# untitled2.net
KiCad netlist of a schematic drawn in EAGLE
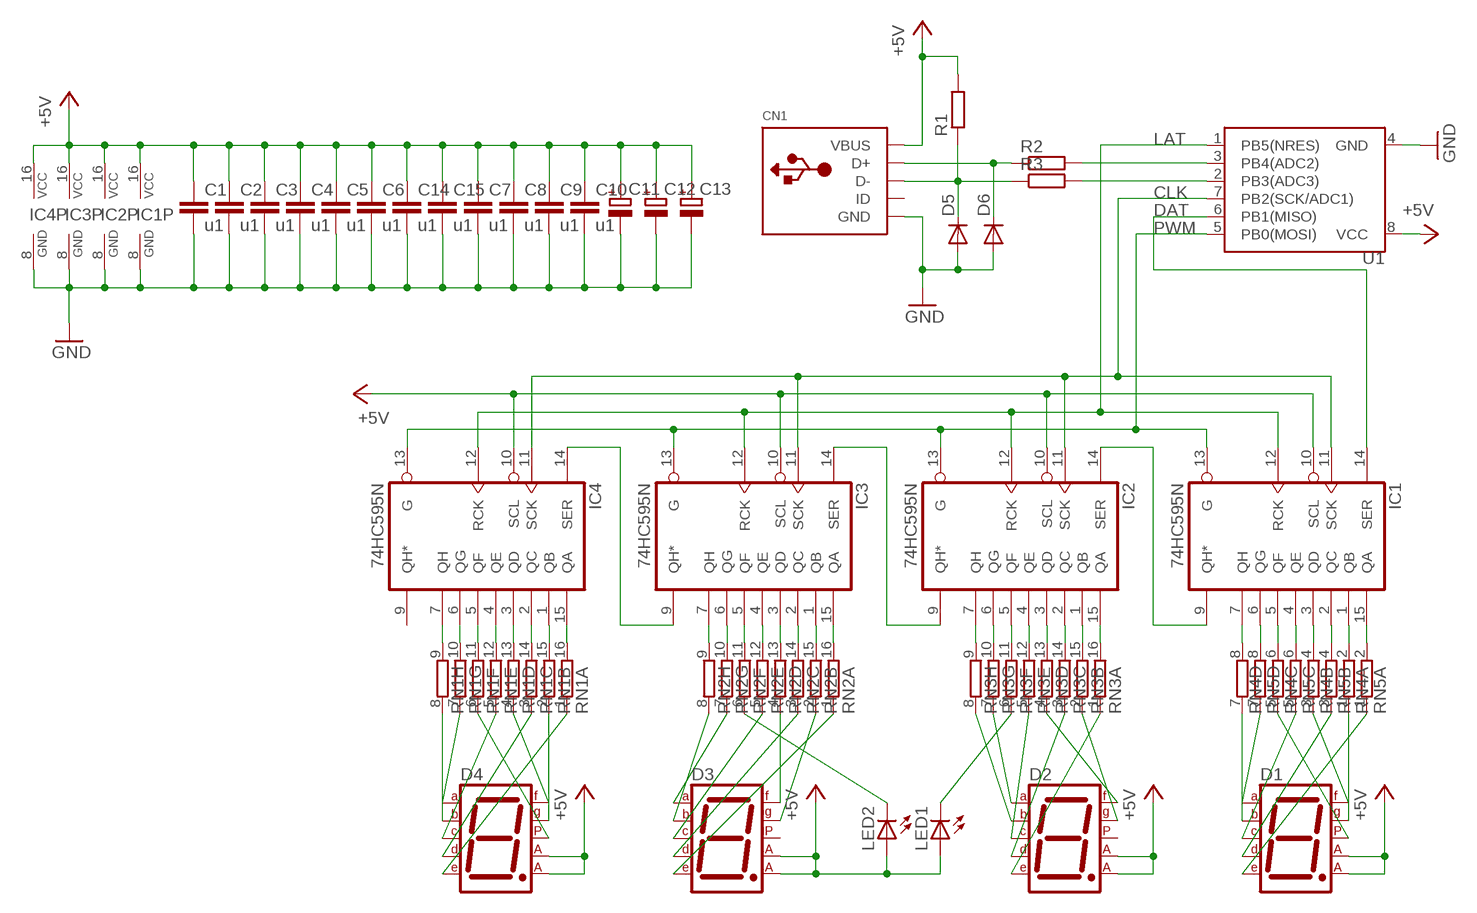
[diagram p0: schematic, sheet 1]

(export (version "E")
  (design (tool "Eeschema 10.0.6"))
  (components
    (comp (ref "C1")
      (value "u1")
      (footprint "eagle-import:C025-025X050")
      (libsource (lib "eagle-import") (part "C-EU025-025X050"))
    )
    (comp (ref "C2")
      (value "u1")
      (footprint "eagle-import:C025-025X050")
      (libsource (lib "eagle-import") (part "C-EU025-025X050"))
    )
    (comp (ref "C3")
      (value "u1")
      (footprint "eagle-import:C025-025X050")
      (libsource (lib "eagle-import") (part "C-EU025-025X050"))
    )
    (comp (ref "C4")
      (value "u1")
      (footprint "eagle-import:C025-025X050")
      (libsource (lib "eagle-import") (part "C-EU025-025X050"))
    )
    (comp (ref "C5")
      (value "u1")
      (footprint "eagle-import:C025-025X050")
      (libsource (lib "eagle-import") (part "C-EU025-025X050"))
    )
    (comp (ref "C6")
      (value "u1")
      (footprint "eagle-import:C025-025X050")
      (libsource (lib "eagle-import") (part "C-EU025-025X050"))
    )
    (comp (ref "C7")
      (value "u1")
      (footprint "eagle-import:C0805K")
      (libsource (lib "eagle-import") (part "C-EUC0805K"))
    )
    (comp (ref "C8")
      (value "u1")
      (footprint "eagle-import:C0805K")
      (libsource (lib "eagle-import") (part "C-EUC0805K"))
    )
    (comp (ref "C9")
      (value "u1")
      (footprint "eagle-import:C0805K")
      (libsource (lib "eagle-import") (part "C-EUC0805K"))
    )
    (comp (ref "C10")
      (value "u1")
      (footprint "eagle-import:C0805K")
      (libsource (lib "eagle-import") (part "C-EUC0805K"))
    )
    (comp (ref "C11")
      (value "CPOL-EUE1.8-4")
      (footprint "eagle-import:E1,8-4")
      (libsource (lib "eagle-import") (part "CPOL-EUE1.8-4"))
    )
    (comp (ref "C12")
      (value "CPOL-EUE2.5-7")
      (footprint "eagle-import:E2,5-7")
      (libsource (lib "eagle-import") (part "CPOL-EUE2.5-7"))
    )
    (comp (ref "C13")
      (value "CPOL-EUE2.5-7")
      (footprint "eagle-import:E2,5-7")
      (libsource (lib "eagle-import") (part "CPOL-EUE2.5-7"))
    )
    (comp (ref "C14")
      (value "u1")
      (footprint "eagle-import:C025-025X050")
      (libsource (lib "eagle-import") (part "C-EU025-025X050"))
    )
    (comp (ref "C15")
      (value "u1")
      (footprint "eagle-import:C025-025X050")
      (libsource (lib "eagle-import") (part "C-EU025-025X050"))
    )
    (comp (ref "CN1")
      (value "USBTHM")
      (footprint "eagle-import:USB-MINIB-THM")
      (libsource (lib "eagle-import") (part "USBTHM"))
    )
    (comp (ref "D1")
      (value "7SEG-CA")
      (footprint "eagle-import:7SEG-13")
      (libsource (lib "eagle-import") (part "7SEG-CA"))
    )
    (comp (ref "D2")
      (value "7SEG-CA")
      (footprint "eagle-import:7SEG-13")
      (libsource (lib "eagle-import") (part "7SEG-CA"))
    )
    (comp (ref "D3")
      (value "7SEG-CA")
      (footprint "eagle-import:7SEG-13")
      (libsource (lib "eagle-import") (part "7SEG-CA"))
    )
    (comp (ref "D4")
      (value "7SEG-CA")
      (footprint "eagle-import:7SEG-13")
      (libsource (lib "eagle-import") (part "7SEG-CA"))
    )
    (comp (ref "D5")
      (value "DIODE-D-7.5")
      (footprint "eagle-import:D-7.5")
      (libsource (lib "eagle-import") (part "DIODE-D-7.5"))
    )
    (comp (ref "D6")
      (value "DIODE-D-7.5")
      (footprint "eagle-import:D-7.5")
      (libsource (lib "eagle-import") (part "DIODE-D-7.5"))
    )
    (comp (ref "IC1")
      (value "74HC595N")
      (footprint "eagle-import:DIL16")
      (libsource (lib "eagle-import") (part "74595NHC"))
    )
    (comp (ref "IC2")
      (value "74HC595N")
      (footprint "eagle-import:DIL16")
      (libsource (lib "eagle-import") (part "74595NHC"))
    )
    (comp (ref "IC3")
      (value "74HC595N")
      (footprint "eagle-import:DIL16")
      (libsource (lib "eagle-import") (part "74595NHC"))
    )
    (comp (ref "IC4")
      (value "74HC595N")
      (footprint "eagle-import:DIL16")
      (libsource (lib "eagle-import") (part "74595NHC"))
    )
    (comp (ref "LED1")
      (value "LED3MM")
      (footprint "eagle-import:LED3MM")
      (libsource (lib "eagle-import") (part "LED3MM"))
    )
    (comp (ref "LED2")
      (value "LED3MM")
      (footprint "eagle-import:LED3MM")
      (libsource (lib "eagle-import") (part "LED3MM"))
    )
    (comp (ref "R1")
      (value "R-EU_0204/7")
      (footprint "eagle-import:0204_7")
      (libsource (lib "eagle-import") (part "R-EU_0204/7"))
    )
    (comp (ref "R2")
      (value "R-EU_0204/7")
      (footprint "eagle-import:0204_7")
      (libsource (lib "eagle-import") (part "R-EU_0204/7"))
    )
    (comp (ref "R3")
      (value "R-EU_0204/7")
      (footprint "eagle-import:0204_7")
      (libsource (lib "eagle-import") (part "R-EU_0204/7"))
    )
    (comp (ref "RN1")
      (value "8R-N")
      (footprint "eagle-import:DIL16")
      (libsource (lib "eagle-import") (part "8R-N"))
    )
    (comp (ref "RN2")
      (value "8R-N")
      (footprint "eagle-import:DIL16")
      (libsource (lib "eagle-import") (part "8R-N"))
    )
    (comp (ref "RN3")
      (value "8R-N")
      (footprint "eagle-import:DIL16")
      (libsource (lib "eagle-import") (part "8R-N"))
    )
    (comp (ref "RN4")
      (value "E4R")
      (footprint "eagle-import:SIL8")
      (libsource (lib "eagle-import") (part "E4R"))
    )
    (comp (ref "RN5")
      (value "E4R")
      (footprint "eagle-import:SIL8")
      (libsource (lib "eagle-import") (part "E4R"))
    )
    (comp (ref "U1")
      (value "ATTINY45ATTINYX5-20-DIP-GAP")
      (footprint "eagle-import:DIL08")
      (libsource (lib "eagle-import") (part "ATTINY45ATTINYX5-20-DIP-GAP"))
    )
  )
  (nets
    (net (code "1") (name "+5V") (class "Default")
      (node (ref "C1") (pin "1") (pinfunction "1_1") (pintype "passive"))
      (node (ref "C10") (pin "1") (pinfunction "1_1") (pintype "passive"))
      (node (ref "C11") (pin "+") (pinfunction "+_+") (pintype "passive"))
      (node (ref "C12") (pin "+") (pinfunction "+_+") (pintype "passive"))
      (node (ref "C13") (pin "+") (pinfunction "+_+") (pintype "passive"))
      (node (ref "C14") (pin "1") (pinfunction "1_1") (pintype "passive"))
      (node (ref "C15") (pin "1") (pinfunction "1_1") (pintype "passive"))
      (node (ref "C2") (pin "1") (pinfunction "1_1") (pintype "passive"))
      (node (ref "C3") (pin "1") (pinfunction "1_1") (pintype "passive"))
      (node (ref "C4") (pin "1") (pinfunction "1_1") (pintype "passive"))
      (node (ref "C5") (pin "1") (pinfunction "1_1") (pintype "passive"))
      (node (ref "C6") (pin "1") (pinfunction "1_1") (pintype "passive"))
      (node (ref "C7") (pin "1") (pinfunction "1_1") (pintype "passive"))
      (node (ref "C8") (pin "1") (pinfunction "1_1") (pintype "passive"))
      (node (ref "C9") (pin "1") (pinfunction "1_1") (pintype "passive"))
      (node (ref "CN1") (pin "VBUS") (pinfunction "VBUS_VBUS") (pintype "power_in"))
      (node (ref "D1") (pin "3") (pinfunction "CA1_3") (pintype "passive"))
      (node (ref "D1") (pin "8") (pinfunction "CA2_8") (pintype "passive"))
      (node (ref "D2") (pin "3") (pinfunction "CA1_3") (pintype "passive"))
      (node (ref "D2") (pin "8") (pinfunction "CA2_8") (pintype "passive"))
      (node (ref "D3") (pin "3") (pinfunction "CA1_3") (pintype "passive"))
      (node (ref "D3") (pin "8") (pinfunction "CA2_8") (pintype "passive"))
      (node (ref "D4") (pin "3") (pinfunction "CA1_3") (pintype "passive"))
      (node (ref "D4") (pin "8") (pinfunction "CA2_8") (pintype "passive"))
      (node (ref "IC1") (pin "10") (pinfunction "SCL_10") (pintype "input"))
      (node (ref "IC1") (pin "16") (pinfunction "VCC_16") (pintype "power_in"))
      (node (ref "IC2") (pin "10") (pinfunction "SCL_10") (pintype "input"))
      (node (ref "IC2") (pin "16") (pinfunction "VCC_16") (pintype "power_in"))
      (node (ref "IC3") (pin "10") (pinfunction "SCL_10") (pintype "input"))
      (node (ref "IC3") (pin "16") (pinfunction "VCC_16") (pintype "power_in"))
      (node (ref "IC4") (pin "10") (pinfunction "SCL_10") (pintype "input"))
      (node (ref "IC4") (pin "16") (pinfunction "VCC_16") (pintype "power_in"))
      (node (ref "LED1") (pin "A") (pinfunction "A_A") (pintype "passive"))
      (node (ref "LED2") (pin "A") (pinfunction "A_A") (pintype "passive"))
      (node (ref "R1") (pin "2") (pinfunction "2_2") (pintype "passive"))
      (node (ref "U1") (pin "8") (pinfunction "VCC_8") (pintype "bidirectional"))
    )
    (net (code "2") (name "/CLK") (class "Default")
      (node (ref "IC1") (pin "11") (pinfunction "SCK_11") (pintype "input"))
      (node (ref "IC2") (pin "11") (pinfunction "SCK_11") (pintype "input"))
      (node (ref "IC3") (pin "11") (pinfunction "SCK_11") (pintype "input"))
      (node (ref "IC4") (pin "11") (pinfunction "SCK_11") (pintype "input"))
      (node (ref "U1") (pin "7") (pinfunction "PB2(SCK/ADC1)_7") (pintype "bidirectional"))
    )
    (net (code "3") (name "/DAT") (class "Default")
      (node (ref "IC1") (pin "14") (pinfunction "SER_14") (pintype "input"))
      (node (ref "U1") (pin "6") (pinfunction "PB1(MISO)_6") (pintype "bidirectional"))
    )
    (net (code "4") (name "/LAT") (class "Default")
      (node (ref "IC1") (pin "12") (pinfunction "RCK_12") (pintype "input"))
      (node (ref "IC2") (pin "12") (pinfunction "RCK_12") (pintype "input"))
      (node (ref "IC3") (pin "12") (pinfunction "RCK_12") (pintype "input"))
      (node (ref "IC4") (pin "12") (pinfunction "RCK_12") (pintype "input"))
      (node (ref "U1") (pin "1") (pinfunction "PB5(NRES)_1") (pintype "bidirectional"))
    )
    (net (code "5") (name "/PWM") (class "Default")
      (node (ref "IC1") (pin "13") (pinfunction "G_13") (pintype "input"))
      (node (ref "IC2") (pin "13") (pinfunction "G_13") (pintype "input"))
      (node (ref "IC3") (pin "13") (pinfunction "G_13") (pintype "input"))
      (node (ref "IC4") (pin "13") (pinfunction "G_13") (pintype "input"))
      (node (ref "U1") (pin "5") (pinfunction "PB0(MOSI)_5") (pintype "bidirectional"))
    )
    (net (code "6") (name "GND") (class "Default")
      (node (ref "C1") (pin "2") (pinfunction "2_2") (pintype "passive"))
      (node (ref "C10") (pin "2") (pinfunction "2_2") (pintype "passive"))
      (node (ref "C11") (pin "-") (pinfunction "-_-") (pintype "passive"))
      (node (ref "C12") (pin "-") (pinfunction "-_-") (pintype "passive"))
      (node (ref "C13") (pin "-") (pinfunction "-_-") (pintype "passive"))
      (node (ref "C14") (pin "2") (pinfunction "2_2") (pintype "passive"))
      (node (ref "C15") (pin "2") (pinfunction "2_2") (pintype "passive"))
      (node (ref "C2") (pin "2") (pinfunction "2_2") (pintype "passive"))
      (node (ref "C3") (pin "2") (pinfunction "2_2") (pintype "passive"))
      (node (ref "C4") (pin "2") (pinfunction "2_2") (pintype "passive"))
      (node (ref "C5") (pin "2") (pinfunction "2_2") (pintype "passive"))
      (node (ref "C6") (pin "2") (pinfunction "2_2") (pintype "passive"))
      (node (ref "C7") (pin "2") (pinfunction "2_2") (pintype "passive"))
      (node (ref "C8") (pin "2") (pinfunction "2_2") (pintype "passive"))
      (node (ref "C9") (pin "2") (pinfunction "2_2") (pintype "passive"))
      (node (ref "CN1") (pin "GND") (pinfunction "GND_GND") (pintype "power_in"))
      (node (ref "D5") (pin "A") (pinfunction "A_A") (pintype "passive"))
      (node (ref "D6") (pin "A") (pinfunction "A_A") (pintype "passive"))
      (node (ref "IC1") (pin "8") (pinfunction "GND_8") (pintype "power_in"))
      (node (ref "IC2") (pin "8") (pinfunction "GND_8") (pintype "power_in"))
      (node (ref "IC3") (pin "8") (pinfunction "GND_8") (pintype "power_in"))
      (node (ref "IC4") (pin "8") (pinfunction "GND_8") (pintype "power_in"))
      (node (ref "U1") (pin "4") (pinfunction "GND_4") (pintype "bidirectional"))
    )
    (net (code "7") (name "Net-(CN1-PadD+)") (class "Default")
      (node (ref "CN1") (pin "D+") (pinfunction "D+_D+") (pintype "bidirectional"))
      (node (ref "D6") (pin "C") (pinfunction "C_C") (pintype "passive"))
      (node (ref "R2") (pin "1") (pinfunction "1_1") (pintype "passive"))
    )
    (net (code "8") (name "Net-(CN1-PadD-)") (class "Default")
      (node (ref "CN1") (pin "D-") (pinfunction "D-_D-") (pintype "bidirectional"))
      (node (ref "D5") (pin "C") (pinfunction "C_C") (pintype "passive"))
      (node (ref "R1") (pin "1") (pinfunction "1_1") (pintype "passive"))
      (node (ref "R3") (pin "1") (pinfunction "1_1") (pintype "passive"))
    )
    (net (code "9") (name "Net-(D1-A)") (class "Default")
      (node (ref "D1") (pin "7") (pinfunction "A_7") (pintype "passive"))
      (node (ref "RN5") (pin "7") (pinfunction "1_7") (pintype "passive"))
    )
    (net (code "10") (name "Net-(D1-B)") (class "Default")
      (node (ref "D1") (pin "6") (pinfunction "B_6") (pintype "passive"))
      (node (ref "RN4") (pin "7") (pinfunction "1_7") (pintype "passive"))
    )
    (net (code "11") (name "Net-(D1-C)") (class "Default")
      (node (ref "D1") (pin "4") (pinfunction "C_4") (pintype "passive"))
      (node (ref "RN5") (pin "5") (pinfunction "1_5") (pintype "passive"))
    )
    (net (code "12") (name "Net-(D1-D)") (class "Default")
      (node (ref "D1") (pin "2") (pinfunction "D_2") (pintype "passive"))
      (node (ref "RN5") (pin "3") (pinfunction "1_3") (pintype "passive"))
    )
    (net (code "13") (name "Net-(D1-DP)") (class "Default")
      (node (ref "D1") (pin "5") (pinfunction "DP_5") (pintype "passive"))
      (node (ref "RN4") (pin "5") (pinfunction "1_5") (pintype "passive"))
    )
    (net (code "14") (name "Net-(D1-E)") (class "Default")
      (node (ref "D1") (pin "1") (pinfunction "E_1") (pintype "passive"))
      (node (ref "RN5") (pin "1") (pinfunction "1_1") (pintype "passive"))
    )
    (net (code "15") (name "Net-(D1-F)") (class "Default")
      (node (ref "D1") (pin "9") (pinfunction "F_9") (pintype "passive"))
      (node (ref "RN4") (pin "3") (pinfunction "1_3") (pintype "passive"))
    )
    (net (code "16") (name "Net-(D1-G)") (class "Default")
      (node (ref "D1") (pin "10") (pinfunction "G_10") (pintype "passive"))
      (node (ref "RN4") (pin "1") (pinfunction "1_1") (pintype "passive"))
    )
    (net (code "17") (name "Net-(D2-A)") (class "Default")
      (node (ref "D2") (pin "7") (pinfunction "A_7") (pintype "passive"))
      (node (ref "RN3") (pin "7") (pinfunction "1_7") (pintype "passive"))
    )
    (net (code "18") (name "Net-(D2-B)") (class "Default")
      (node (ref "D2") (pin "6") (pinfunction "B_6") (pintype "passive"))
      (node (ref "RN3") (pin "8") (pinfunction "1_8") (pintype "passive"))
    )
    (net (code "19") (name "Net-(D2-C)") (class "Default")
      (node (ref "D2") (pin "4") (pinfunction "C_4") (pintype "passive"))
      (node (ref "RN3") (pin "5") (pinfunction "1_5") (pintype "passive"))
    )
    (net (code "20") (name "Net-(D2-D)") (class "Default")
      (node (ref "D2") (pin "2") (pinfunction "D_2") (pintype "passive"))
      (node (ref "RN3") (pin "3") (pinfunction "1_3") (pintype "passive"))
    )
    (net (code "21") (name "Net-(D2-E)") (class "Default")
      (node (ref "D2") (pin "1") (pinfunction "E_1") (pintype "passive"))
      (node (ref "RN3") (pin "1") (pinfunction "1_1") (pintype "passive"))
    )
    (net (code "22") (name "Net-(D2-F)") (class "Default")
      (node (ref "D2") (pin "9") (pinfunction "F_9") (pintype "passive"))
      (node (ref "RN3") (pin "4") (pinfunction "1_4") (pintype "passive"))
    )
    (net (code "23") (name "Net-(D2-G)") (class "Default")
      (node (ref "D2") (pin "10") (pinfunction "G_10") (pintype "passive"))
      (node (ref "RN3") (pin "2") (pinfunction "1_2") (pintype "passive"))
    )
    (net (code "24") (name "Net-(D3-A)") (class "Default")
      (node (ref "D3") (pin "7") (pinfunction "A_7") (pintype "passive"))
      (node (ref "RN2") (pin "7") (pinfunction "1_7") (pintype "passive"))
    )
    (net (code "25") (name "Net-(D3-B)") (class "Default")
      (node (ref "D3") (pin "6") (pinfunction "B_6") (pintype "passive"))
      (node (ref "RN2") (pin "8") (pinfunction "1_8") (pintype "passive"))
    )
    (net (code "26") (name "Net-(D3-C)") (class "Default")
      (node (ref "D3") (pin "4") (pinfunction "C_4") (pintype "passive"))
      (node (ref "RN2") (pin "5") (pinfunction "1_5") (pintype "passive"))
    )
    (net (code "27") (name "Net-(D3-D)") (class "Default")
      (node (ref "D3") (pin "2") (pinfunction "D_2") (pintype "passive"))
      (node (ref "RN2") (pin "3") (pinfunction "1_3") (pintype "passive"))
    )
    (net (code "28") (name "Net-(D3-E)") (class "Default")
      (node (ref "D3") (pin "1") (pinfunction "E_1") (pintype "passive"))
      (node (ref "RN2") (pin "1") (pinfunction "1_1") (pintype "passive"))
    )
    (net (code "29") (name "Net-(D3-F)") (class "Default")
      (node (ref "D3") (pin "9") (pinfunction "F_9") (pintype "passive"))
      (node (ref "RN2") (pin "4") (pinfunction "1_4") (pintype "passive"))
    )
    (net (code "30") (name "Net-(D3-G)") (class "Default")
      (node (ref "D3") (pin "10") (pinfunction "G_10") (pintype "passive"))
      (node (ref "RN2") (pin "2") (pinfunction "1_2") (pintype "passive"))
    )
    (net (code "31") (name "Net-(D4-A)") (class "Default")
      (node (ref "D4") (pin "7") (pinfunction "A_7") (pintype "passive"))
      (node (ref "RN1") (pin "7") (pinfunction "1_7") (pintype "passive"))
    )
    (net (code "32") (name "Net-(D4-B)") (class "Default")
      (node (ref "D4") (pin "6") (pinfunction "B_6") (pintype "passive"))
      (node (ref "RN1") (pin "8") (pinfunction "1_8") (pintype "passive"))
    )
    (net (code "33") (name "Net-(D4-C)") (class "Default")
      (node (ref "D4") (pin "4") (pinfunction "C_4") (pintype "passive"))
      (node (ref "RN1") (pin "5") (pinfunction "1_5") (pintype "passive"))
    )
    (net (code "34") (name "Net-(D4-D)") (class "Default")
      (node (ref "D4") (pin "2") (pinfunction "D_2") (pintype "passive"))
      (node (ref "RN1") (pin "3") (pinfunction "1_3") (pintype "passive"))
    )
    (net (code "35") (name "Net-(D4-DP)") (class "Default")
      (node (ref "D4") (pin "5") (pinfunction "DP_5") (pintype "passive"))
      (node (ref "RN1") (pin "6") (pinfunction "1_6") (pintype "passive"))
    )
    (net (code "36") (name "Net-(D4-E)") (class "Default")
      (node (ref "D4") (pin "1") (pinfunction "E_1") (pintype "passive"))
      (node (ref "RN1") (pin "1") (pinfunction "1_1") (pintype "passive"))
    )
    (net (code "37") (name "Net-(D4-F)") (class "Default")
      (node (ref "D4") (pin "9") (pinfunction "F_9") (pintype "passive"))
      (node (ref "RN1") (pin "4") (pinfunction "1_4") (pintype "passive"))
    )
    (net (code "38") (name "Net-(D4-G)") (class "Default")
      (node (ref "D4") (pin "10") (pinfunction "G_10") (pintype "passive"))
      (node (ref "RN1") (pin "2") (pinfunction "1_2") (pintype "passive"))
    )
    (net (code "39") (name "Net-(IC1A-QA)") (class "Default")
      (node (ref "IC1") (pin "15") (pinfunction "QA_15") (pintype "tri_state"))
      (node (ref "RN5") (pin "2") (pinfunction "2_2") (pintype "passive"))
    )
    (net (code "40") (name "Net-(IC1A-QB)") (class "Default")
      (node (ref "IC1") (pin "1") (pinfunction "QB_1") (pintype "tri_state"))
      (node (ref "RN4") (pin "2") (pinfunction "2_2") (pintype "passive"))
    )
    (net (code "41") (name "Net-(IC1A-QC)") (class "Default")
      (node (ref "IC1") (pin "2") (pinfunction "QC_2") (pintype "tri_state"))
      (node (ref "RN5") (pin "4") (pinfunction "2_4") (pintype "passive"))
    )
    (net (code "42") (name "Net-(IC1A-QD)") (class "Default")
      (node (ref "IC1") (pin "3") (pinfunction "QD_3") (pintype "tri_state"))
      (node (ref "RN4") (pin "4") (pinfunction "2_4") (pintype "passive"))
    )
    (net (code "43") (name "Net-(IC1A-QE)") (class "Default")
      (node (ref "IC1") (pin "4") (pinfunction "QE_4") (pintype "tri_state"))
      (node (ref "RN5") (pin "6") (pinfunction "2_6") (pintype "passive"))
    )
    (net (code "44") (name "Net-(IC1A-QF)") (class "Default")
      (node (ref "IC1") (pin "5") (pinfunction "QF_5") (pintype "tri_state"))
      (node (ref "RN4") (pin "6") (pinfunction "2_6") (pintype "passive"))
    )
    (net (code "45") (name "Net-(IC1A-QG)") (class "Default")
      (node (ref "IC1") (pin "6") (pinfunction "QG_6") (pintype "tri_state"))
      (node (ref "RN5") (pin "8") (pinfunction "2_8") (pintype "passive"))
    )
    (net (code "46") (name "Net-(IC1A-QH)") (class "Default")
      (node (ref "IC1") (pin "7") (pinfunction "QH_7") (pintype "tri_state"))
      (node (ref "RN4") (pin "8") (pinfunction "2_8") (pintype "passive"))
    )
    (net (code "47") (name "Net-(IC1A-QH*)") (class "Default")
      (node (ref "IC1") (pin "9") (pinfunction "QH*_9") (pintype "tri_state"))
      (node (ref "IC2") (pin "14") (pinfunction "SER_14") (pintype "input"))
    )
    (net (code "48") (name "Net-(IC2A-QA)") (class "Default")
      (node (ref "IC2") (pin "15") (pinfunction "QA_15") (pintype "tri_state"))
      (node (ref "RN3") (pin "16") (pinfunction "2_16") (pintype "passive"))
    )
    (net (code "49") (name "Net-(IC2A-QB)") (class "Default")
      (node (ref "IC2") (pin "1") (pinfunction "QB_1") (pintype "tri_state"))
      (node (ref "RN3") (pin "15") (pinfunction "2_15") (pintype "passive"))
    )
    (net (code "50") (name "Net-(IC2A-QC)") (class "Default")
      (node (ref "IC2") (pin "2") (pinfunction "QC_2") (pintype "tri_state"))
      (node (ref "RN3") (pin "14") (pinfunction "2_14") (pintype "passive"))
    )
    (net (code "51") (name "Net-(IC2A-QD)") (class "Default")
      (node (ref "IC2") (pin "3") (pinfunction "QD_3") (pintype "tri_state"))
      (node (ref "RN3") (pin "13") (pinfunction "2_13") (pintype "passive"))
    )
    (net (code "52") (name "Net-(IC2A-QE)") (class "Default")
      (node (ref "IC2") (pin "4") (pinfunction "QE_4") (pintype "tri_state"))
      (node (ref "RN3") (pin "12") (pinfunction "2_12") (pintype "passive"))
    )
    (net (code "53") (name "Net-(IC2A-QF)") (class "Default")
      (node (ref "IC2") (pin "5") (pinfunction "QF_5") (pintype "tri_state"))
      (node (ref "RN3") (pin "11") (pinfunction "2_11") (pintype "passive"))
    )
    (net (code "54") (name "Net-(IC2A-QG)") (class "Default")
      (node (ref "IC2") (pin "6") (pinfunction "QG_6") (pintype "tri_state"))
      (node (ref "RN3") (pin "10") (pinfunction "2_10") (pintype "passive"))
    )
    (net (code "55") (name "Net-(IC2A-QH)") (class "Default")
      (node (ref "IC2") (pin "7") (pinfunction "QH_7") (pintype "tri_state"))
      (node (ref "RN3") (pin "9") (pinfunction "2_9") (pintype "passive"))
    )
    (net (code "56") (name "Net-(IC2A-QH*)") (class "Default")
      (node (ref "IC2") (pin "9") (pinfunction "QH*_9") (pintype "tri_state"))
      (node (ref "IC3") (pin "14") (pinfunction "SER_14") (pintype "input"))
    )
    (net (code "57") (name "Net-(IC3A-QA)") (class "Default")
      (node (ref "IC3") (pin "15") (pinfunction "QA_15") (pintype "tri_state"))
      (node (ref "RN2") (pin "16") (pinfunction "2_16") (pintype "passive"))
    )
    (net (code "58") (name "Net-(IC3A-QB)") (class "Default")
      (node (ref "IC3") (pin "1") (pinfunction "QB_1") (pintype "tri_state"))
      (node (ref "RN2") (pin "15") (pinfunction "2_15") (pintype "passive"))
    )
    (net (code "59") (name "Net-(IC3A-QC)") (class "Default")
      (node (ref "IC3") (pin "2") (pinfunction "QC_2") (pintype "tri_state"))
      (node (ref "RN2") (pin "14") (pinfunction "2_14") (pintype "passive"))
    )
    (net (code "60") (name "Net-(IC3A-QD)") (class "Default")
      (node (ref "IC3") (pin "3") (pinfunction "QD_3") (pintype "tri_state"))
      (node (ref "RN2") (pin "13") (pinfunction "2_13") (pintype "passive"))
    )
    (net (code "61") (name "Net-(IC3A-QE)") (class "Default")
      (node (ref "IC3") (pin "4") (pinfunction "QE_4") (pintype "tri_state"))
      (node (ref "RN2") (pin "12") (pinfunction "2_12") (pintype "passive"))
    )
    (net (code "62") (name "Net-(IC3A-QF)") (class "Default")
      (node (ref "IC3") (pin "5") (pinfunction "QF_5") (pintype "tri_state"))
      (node (ref "RN2") (pin "11") (pinfunction "2_11") (pintype "passive"))
    )
    (net (code "63") (name "Net-(IC3A-QG)") (class "Default")
      (node (ref "IC3") (pin "6") (pinfunction "QG_6") (pintype "tri_state"))
      (node (ref "RN2") (pin "10") (pinfunction "2_10") (pintype "passive"))
    )
    (net (code "64") (name "Net-(IC3A-QH)") (class "Default")
      (node (ref "IC3") (pin "7") (pinfunction "QH_7") (pintype "tri_state"))
      (node (ref "RN2") (pin "9") (pinfunction "2_9") (pintype "passive"))
    )
    (net (code "65") (name "Net-(IC3A-QH*)") (class "Default")
      (node (ref "IC3") (pin "9") (pinfunction "QH*_9") (pintype "tri_state"))
      (node (ref "IC4") (pin "14") (pinfunction "SER_14") (pintype "input"))
    )
    (net (code "66") (name "Net-(IC4A-QA)") (class "Default")
      (node (ref "IC4") (pin "15") (pinfunction "QA_15") (pintype "tri_state"))
      (node (ref "RN1") (pin "16") (pinfunction "2_16") (pintype "passive"))
    )
    (net (code "67") (name "Net-(IC4A-QB)") (class "Default")
      (node (ref "IC4") (pin "1") (pinfunction "QB_1") (pintype "tri_state"))
      (node (ref "RN1") (pin "15") (pinfunction "2_15") (pintype "passive"))
    )
    (net (code "68") (name "Net-(IC4A-QC)") (class "Default")
      (node (ref "IC4") (pin "2") (pinfunction "QC_2") (pintype "tri_state"))
      (node (ref "RN1") (pin "14") (pinfunction "2_14") (pintype "passive"))
    )
    (net (code "69") (name "Net-(IC4A-QD)") (class "Default")
      (node (ref "IC4") (pin "3") (pinfunction "QD_3") (pintype "tri_state"))
      (node (ref "RN1") (pin "13") (pinfunction "2_13") (pintype "passive"))
    )
    (net (code "70") (name "Net-(IC4A-QE)") (class "Default")
      (node (ref "IC4") (pin "4") (pinfunction "QE_4") (pintype "tri_state"))
      (node (ref "RN1") (pin "12") (pinfunction "2_12") (pintype "passive"))
    )
    (net (code "71") (name "Net-(IC4A-QF)") (class "Default")
      (node (ref "IC4") (pin "5") (pinfunction "QF_5") (pintype "tri_state"))
      (node (ref "RN1") (pin "11") (pinfunction "2_11") (pintype "passive"))
    )
    (net (code "72") (name "Net-(IC4A-QG)") (class "Default")
      (node (ref "IC4") (pin "6") (pinfunction "QG_6") (pintype "tri_state"))
      (node (ref "RN1") (pin "10") (pinfunction "2_10") (pintype "passive"))
    )
    (net (code "73") (name "Net-(IC4A-QH)") (class "Default")
      (node (ref "IC4") (pin "7") (pinfunction "QH_7") (pintype "tri_state"))
      (node (ref "RN1") (pin "9") (pinfunction "2_9") (pintype "passive"))
    )
    (net (code "74") (name "Net-(LED1-C)") (class "Default")
      (node (ref "LED1") (pin "K") (pinfunction "C_K") (pintype "passive"))
      (node (ref "RN3") (pin "6") (pinfunction "1_6") (pintype "passive"))
    )
    (net (code "75") (name "Net-(LED2-C)") (class "Default")
      (node (ref "LED2") (pin "K") (pinfunction "C_K") (pintype "passive"))
      (node (ref "RN2") (pin "6") (pinfunction "1_6") (pintype "passive"))
    )
    (net (code "76") (name "Net-(U1-PB3(ADC3))") (class "Default")
      (node (ref "R3") (pin "2") (pinfunction "2_2") (pintype "passive"))
      (node (ref "U1") (pin "2") (pinfunction "PB3(ADC3)_2") (pintype "bidirectional"))
    )
    (net (code "77") (name "Net-(U1-PB4(ADC2))") (class "Default")
      (node (ref "R2") (pin "2") (pinfunction "2_2") (pintype "passive"))
      (node (ref "U1") (pin "3") (pinfunction "PB4(ADC2)_3") (pintype "bidirectional"))
    )
    (net (code "78") (name "unconnected-(CN1-PadID)") (class "Default")
      (node (ref "CN1") (pin "ID") (pinfunction "ID_ID") (pintype "bidirectional"))
    )
    (net (code "79") (name "unconnected-(D2-DP-Pad5)") (class "Default")
      (node (ref "D2") (pin "5") (pinfunction "DP_5") (pintype "passive"))
    )
    (net (code "80") (name "unconnected-(D3-DP-Pad5)") (class "Default")
      (node (ref "D3") (pin "5") (pinfunction "DP_5") (pintype "passive"))
    )
    (net (code "81") (name "unconnected-(IC4A-QH*-Pad9)") (class "Default")
      (node (ref "IC4") (pin "9") (pinfunction "QH*_9") (pintype "tri_state"))
    )
  )
)
